# PSoC.net
KiCad netlist of a schematic drawn in Altium Designer
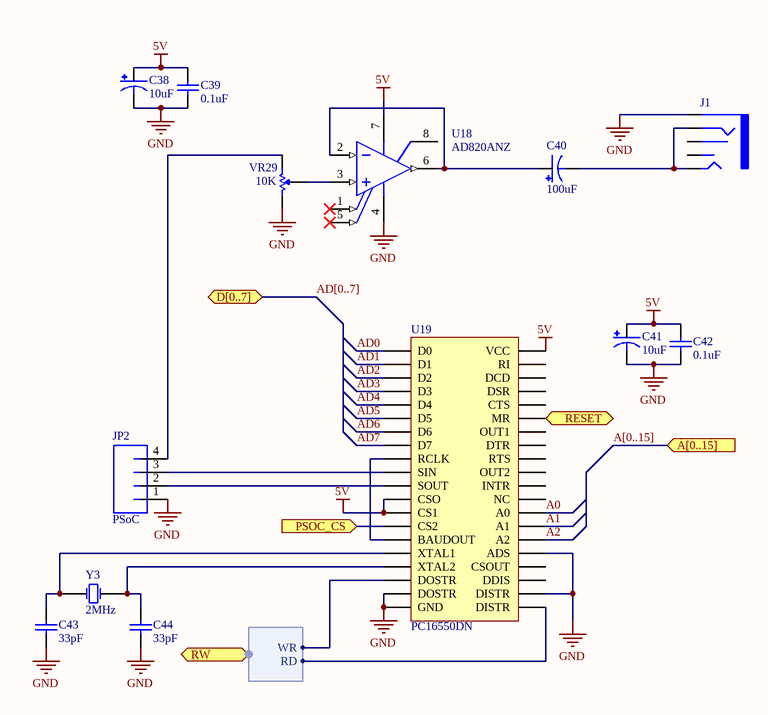
[diagram p0: PSoC.SchDoc]

(export (version "E")
  (design (tool "Eeschema 10.0.6"))
  (components
    (comp (ref "C38")
      (value "10uF")
      (footprint "CPOL-RADIAL")
      (libsource (lib "Components") (part "PolarizedCap"))
    )
    (comp (ref "C39") (value "0.1uF") (footprint "CAP-PTH") (libsource (lib "Components") (part "Cap")))
    (comp (ref "C40")
      (value "100uF")
      (footprint "CPOL-RADIAL-100UF-25V")
      (libsource (lib "Components") (part "PolarizedCap-100uF"))
    )
    (comp (ref "C41")
      (value "10uF")
      (footprint "CPOL-RADIAL")
      (libsource (lib "Components") (part "PolarizedCap"))
    )
    (comp (ref "C42") (value "0.1uF") (footprint "CAP-PTH") (libsource (lib "Components") (part "Cap")))
    (comp (ref "C43") (value "33pF") (footprint "CAP-PTH") (libsource (lib "Components") (part "Cap")))
    (comp (ref "C44") (value "33pF") (footprint "CAP-PTH") (libsource (lib "Components") (part "Cap")))
    (comp (ref "J1") (value "~") (footprint "AUDIO_JACK") (libsource (lib "Components") (part "AudioJack")))
    (comp (ref "JP2")
      (value "PSoC")
      (footprint "JST-PH-4-PTH-HORZ")
      (fields
        (field (name "PARTNUMBER") "S4B-PH-K-S(LF)(SN)")
        (field (name "MANUFACTURER") "JST Sales America Inc.")
      )
      (libsource (lib "Connectors") (part "JST_PH_4_HORZ"))
    )
    (comp (ref "U18")
      (value "AD820ANZ")
      (footprint "ADI-N-8")
      (fields (field (name "MANUFACTURER") "Analog Devices") (field (name "GENERIC PART NUMBER") "AD820"))
      (libsource (lib "Altium Content Vault") (part "ADI-AD820-N-8"))
    )
    (comp (ref "U19")
      (value "PC16550DN")
      (footprint "PDIP-40")
      (fields (field (name "MANUFACTURER") "Texas Instruments"))
      (libsource (lib "ICs") (part "PC16550DN"))
    )
    (comp (ref "VR29")
      (value "10K")
      (footprint "ROTARY_POT")
      (libsource (lib "Components") (part "RotaryPot"))
    )
    (comp (ref "Y3") (value "2MHz") (footprint "CRYSTAL_PTH") (libsource (lib "Components") (part "Crystal")))
  )
  (nets
    (net (code "15") (name "/A0") (class "Default")
      (node (ref "U19") (pin "28") (pinfunction "A0_28") (pintype "passive"))
    )
    (net (code "16") (name "/A1") (class "Default")
      (node (ref "U19") (pin "27") (pinfunction "A1_27") (pintype "passive"))
    )
    (net (code "17") (name "/A2") (class "Default")
      (node (ref "U19") (pin "26") (pinfunction "A2_26") (pintype "passive"))
    )
    (net (code "18") (name "/AD0") (class "Default")
      (node (ref "U19") (pin "1") (pinfunction "D0_1") (pintype "passive"))
    )
    (net (code "19") (name "/AD1") (class "Default")
      (node (ref "U19") (pin "2") (pinfunction "D1_2") (pintype "passive"))
    )
    (net (code "20") (name "/AD2") (class "Default")
      (node (ref "U19") (pin "3") (pinfunction "D2_3") (pintype "passive"))
    )
    (net (code "21") (name "/AD3") (class "Default")
      (node (ref "U19") (pin "4") (pinfunction "D3_4") (pintype "passive"))
    )
    (net (code "22") (name "/AD4") (class "Default")
      (node (ref "U19") (pin "5") (pinfunction "D4_5") (pintype "passive"))
    )
    (net (code "23") (name "/AD5") (class "Default")
      (node (ref "U19") (pin "6") (pinfunction "D5_6") (pintype "passive"))
    )
    (net (code "24") (name "/AD6") (class "Default")
      (node (ref "U19") (pin "7") (pinfunction "D6_7") (pintype "passive"))
    )
    (net (code "25") (name "/AD7") (class "Default")
      (node (ref "U19") (pin "8") (pinfunction "D7_8") (pintype "passive"))
    )
    (net (code "28") (name "/PSOC_CS") (class "Default")
      (node (ref "U19") (pin "14") (pinfunction "CS2_14") (pintype "passive"))
    )
    (net (code "29") (name "/RD") (class "Default")
      (node (ref "U19") (pin "21") (pinfunction "DISTR_21") (pintype "passive"))
    )
    (net (code "30") (name "/RESET") (class "Default")
      (node (ref "U19") (pin "35") (pinfunction "MR_35") (pintype "passive"))
    )
    (net (code "31") (name "/WR") (class "Default")
      (node (ref "U19") (pin "18") (pinfunction "DOSTR_18") (pintype "passive"))
    )
    (net (code "33") (name "5V") (class "Default")
      (node (ref "C38") (pin "1") (pinfunction "+_1") (pintype "passive"))
      (node (ref "C39") (pin "1") (pinfunction "1_1") (pintype "passive"))
      (node (ref "C41") (pin "1") (pinfunction "+_1") (pintype "passive"))
      (node (ref "C42") (pin "1") (pinfunction "1_1") (pintype "passive"))
      (node (ref "U18") (pin "7") (pinfunction "+VS_7") (pintype "power_in"))
      (node (ref "U19") (pin "12") (pinfunction "CSO_12") (pintype "passive"))
      (node (ref "U19") (pin "13") (pinfunction "CS1_13") (pintype "passive"))
      (node (ref "U19") (pin "40") (pinfunction "VCC_40") (pintype "passive"))
    )
    (net (code "34") (name "GND") (class "Default")
      (node (ref "C38") (pin "2") (pinfunction "-_2") (pintype "passive"))
      (node (ref "C39") (pin "2") (pinfunction "2_2") (pintype "passive"))
      (node (ref "C41") (pin "2") (pinfunction "-_2") (pintype "passive"))
      (node (ref "C42") (pin "2") (pinfunction "2_2") (pintype "passive"))
      (node (ref "C43") (pin "2") (pinfunction "2_2") (pintype "passive"))
      (node (ref "C44") (pin "2") (pinfunction "2_2") (pintype "passive"))
      (node (ref "J1") (pin "SLEEVE") (pinfunction "SLEEVE_SLEEVE") (pintype "passive"))
      (node (ref "JP2") (pin "1") (pinfunction "1_1") (pintype "passive"))
      (node (ref "U18") (pin "4") (pinfunction "-VS_4") (pintype "power_in"))
      (node (ref "U19") (pin "19") (pinfunction "DOSTR_19") (pintype "passive"))
      (node (ref "U19") (pin "20") (pinfunction "GND_20") (pintype "passive"))
      (node (ref "U19") (pin "22") (pinfunction "DISTR_22") (pintype "passive"))
      (node (ref "U19") (pin "25") (pinfunction "ADS_25") (pintype "passive"))
      (node (ref "VR29") (pin "3") (pinfunction "3_3") (pintype "passive"))
    )
    (net (code "35") (name "Net-(C40-+)") (class "Default")
      (node (ref "C40") (pin "1") (pinfunction "+_1") (pintype "passive"))
      (node (ref "U18") (pin "2") (pinfunction "-IN_2") (pintype "input"))
      (node (ref "U18") (pin "6") (pinfunction "VOUT_6") (pintype "output"))
    )
    (net (code "36") (name "Net-(C40--)") (class "Default")
      (node (ref "C40") (pin "2") (pinfunction "-_2") (pintype "passive"))
      (node (ref "J1") (pin "RING") (pinfunction "RING_RING") (pintype "passive"))
      (node (ref "J1") (pin "TIP") (pinfunction "TIP_TIP") (pintype "passive"))
    )
    (net (code "37") (name "Net-(JP2-Pad4)") (class "Default")
      (node (ref "JP2") (pin "4") (pinfunction "4_4") (pintype "passive"))
      (node (ref "VR29") (pin "1") (pinfunction "1_1") (pintype "passive"))
    )
    (net (code "38") (name "Net-(U18-+IN)") (class "Default")
      (node (ref "U18") (pin "3") (pinfunction "+IN_3") (pintype "input"))
      (node (ref "VR29") (pin "2") (pinfunction "2_2") (pintype "passive"))
    )
    (net (code "39") (name "Net-(U19-BAUDOUT)") (class "Default")
      (node (ref "U19") (pin "15") (pinfunction "BAUDOUT_15") (pintype "passive"))
      (node (ref "U19") (pin "9") (pinfunction "RCLK_9") (pintype "passive"))
    )
    (net (code "40") (name "Net-(U19-SIN)") (class "Default")
      (node (ref "JP2") (pin "3") (pinfunction "3_3") (pintype "passive"))
      (node (ref "U19") (pin "10") (pinfunction "SIN_10") (pintype "passive"))
    )
    (net (code "41") (name "Net-(U19-SOUT)") (class "Default")
      (node (ref "JP2") (pin "2") (pinfunction "2_2") (pintype "passive"))
      (node (ref "U19") (pin "11") (pinfunction "SOUT_11") (pintype "passive"))
    )
    (net (code "42") (name "Net-(U19-XTAL1)") (class "Default")
      (node (ref "C43") (pin "1") (pinfunction "1_1") (pintype "passive"))
      (node (ref "U19") (pin "16") (pinfunction "XTAL1_16") (pintype "passive"))
      (node (ref "Y3") (pin "1") (pinfunction "X1_1") (pintype "passive"))
    )
    (net (code "43") (name "Net-(U19-XTAL2)") (class "Default")
      (node (ref "C44") (pin "1") (pinfunction "1_1") (pintype "passive"))
      (node (ref "U19") (pin "17") (pinfunction "XTAL2_17") (pintype "passive"))
      (node (ref "Y3") (pin "2") (pinfunction "X2_2") (pintype "passive"))
    )
    (net (code "44") (name "unconnected-(J1-PadRSH)") (class "Default")
      (node (ref "J1") (pin "RSH") (pinfunction "RSH_RSH") (pintype "passive"))
    )
    (net (code "45") (name "unconnected-(J1-PadTSH)") (class "Default")
      (node (ref "J1") (pin "TSH") (pinfunction "TSH_TSH") (pintype "passive"))
    )
    (net (code "46") (name "unconnected-(U18-NC-Pad8)") (class "Default")
      (node (ref "U18") (pin "8") (pinfunction "NC_8") (pintype "passive"))
    )
    (net (code "47") (name "unconnected-(U18-NULL-Pad1)") (class "Default")
      (node (ref "U18") (pin "1") (pinfunction "NULL_1") (pintype "input+no_connect"))
    )
    (net (code "48") (name "unconnected-(U18-NULL-Pad5)") (class "Default")
      (node (ref "U18") (pin "5") (pinfunction "NULL_5") (pintype "input+no_connect"))
    )
    (net (code "49") (name "unconnected-(U19-CSOUT-Pad24)") (class "Default")
      (node (ref "U19") (pin "24") (pinfunction "CSOUT_24") (pintype "passive"))
    )
    (net (code "50") (name "unconnected-(U19-CTS-Pad36)") (class "Default")
      (node (ref "U19") (pin "36") (pinfunction "CTS_36") (pintype "passive"))
    )
    (net (code "51") (name "unconnected-(U19-DCD-Pad38)") (class "Default")
      (node (ref "U19") (pin "38") (pinfunction "DCD_38") (pintype "passive"))
    )
    (net (code "52") (name "unconnected-(U19-DDIS-Pad23)") (class "Default")
      (node (ref "U19") (pin "23") (pinfunction "DDIS_23") (pintype "passive"))
    )
    (net (code "53") (name "unconnected-(U19-DSR-Pad37)") (class "Default")
      (node (ref "U19") (pin "37") (pinfunction "DSR_37") (pintype "passive"))
    )
    (net (code "54") (name "unconnected-(U19-DTR-Pad33)") (class "Default")
      (node (ref "U19") (pin "33") (pinfunction "DTR_33") (pintype "passive"))
    )
    (net (code "55") (name "unconnected-(U19-INTR-Pad30)") (class "Default")
      (node (ref "U19") (pin "30") (pinfunction "INTR_30") (pintype "passive"))
    )
    (net (code "56") (name "unconnected-(U19-NC-Pad29)") (class "Default")
      (node (ref "U19") (pin "29") (pinfunction "NC_29") (pintype "passive"))
    )
    (net (code "57") (name "unconnected-(U19-OUT1-Pad34)") (class "Default")
      (node (ref "U19") (pin "34") (pinfunction "OUT1_34") (pintype "passive"))
    )
    (net (code "58") (name "unconnected-(U19-OUT2-Pad31)") (class "Default")
      (node (ref "U19") (pin "31") (pinfunction "OUT2_31") (pintype "passive"))
    )
    (net (code "59") (name "unconnected-(U19-RI-Pad39)") (class "Default")
      (node (ref "U19") (pin "39") (pinfunction "RI_39") (pintype "passive"))
    )
    (net (code "60") (name "unconnected-(U19-RTS-Pad32)") (class "Default")
      (node (ref "U19") (pin "32") (pinfunction "RTS_32") (pintype "passive"))
    )
  )
)
